# P3_POWER.net
KiCad netlist of a schematic drawn in Altium Designer
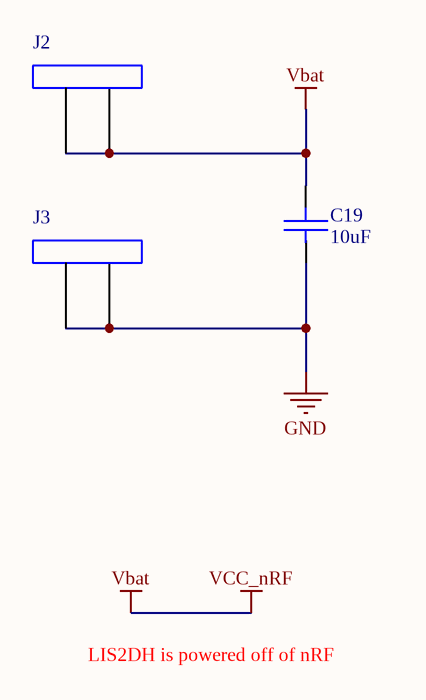
[diagram p0: P3_POWER.SchDoc]

(export (version "E")
  (design (tool "Eeschema 10.0.6"))
  (components
    (comp (ref "C19")
      (value "10uF")
      (footprint "CAPC0603(1608)_N")
      (fields (field (name "TOLERANCE") "+/-20%") (field (name "Comment") "CAP CER 10UF 6.3V 20% X5R 0603"))
      (libsource (lib "Arena_Lib") (part "CAP"))
    )
    (comp (ref "J2")
      (value "Battery Contact Positive Low Profile")
      (footprint "BATT_POS_SPUTNIK")
      (libsource (lib "Arena_Lib") (part "BATTERY_CONTACT"))
    )
    (comp (ref "J3")
      (value "Coin Cell Battery Negative Contact")
      (footprint "BATT_NEG")
      (libsource (lib "Arena_Lib") (part "BATTERY_CONTACT"))
    )
  )
  (nets
    (net (code "1") (name "GND") (class "Default")
      (node (ref "C19") (pin "1") (pinfunction "1_1") (pintype "passive"))
      (node (ref "J3") (pin "1") (pintype "passive"))
      (node (ref "J3") (pin "2") (pintype "passive"))
    )
    (net (code "2") (name "VCC_nRF") (class "Default")
      (node (ref "C19") (pin "2") (pinfunction "2_2") (pintype "passive"))
      (node (ref "J2") (pin "1") (pintype "passive"))
      (node (ref "J2") (pin "2") (pintype "passive"))
    )
  )
)
